# EFT_X003_Y003_X007.net
KiCad netlist of a schematic drawn in EasyEDA Pro
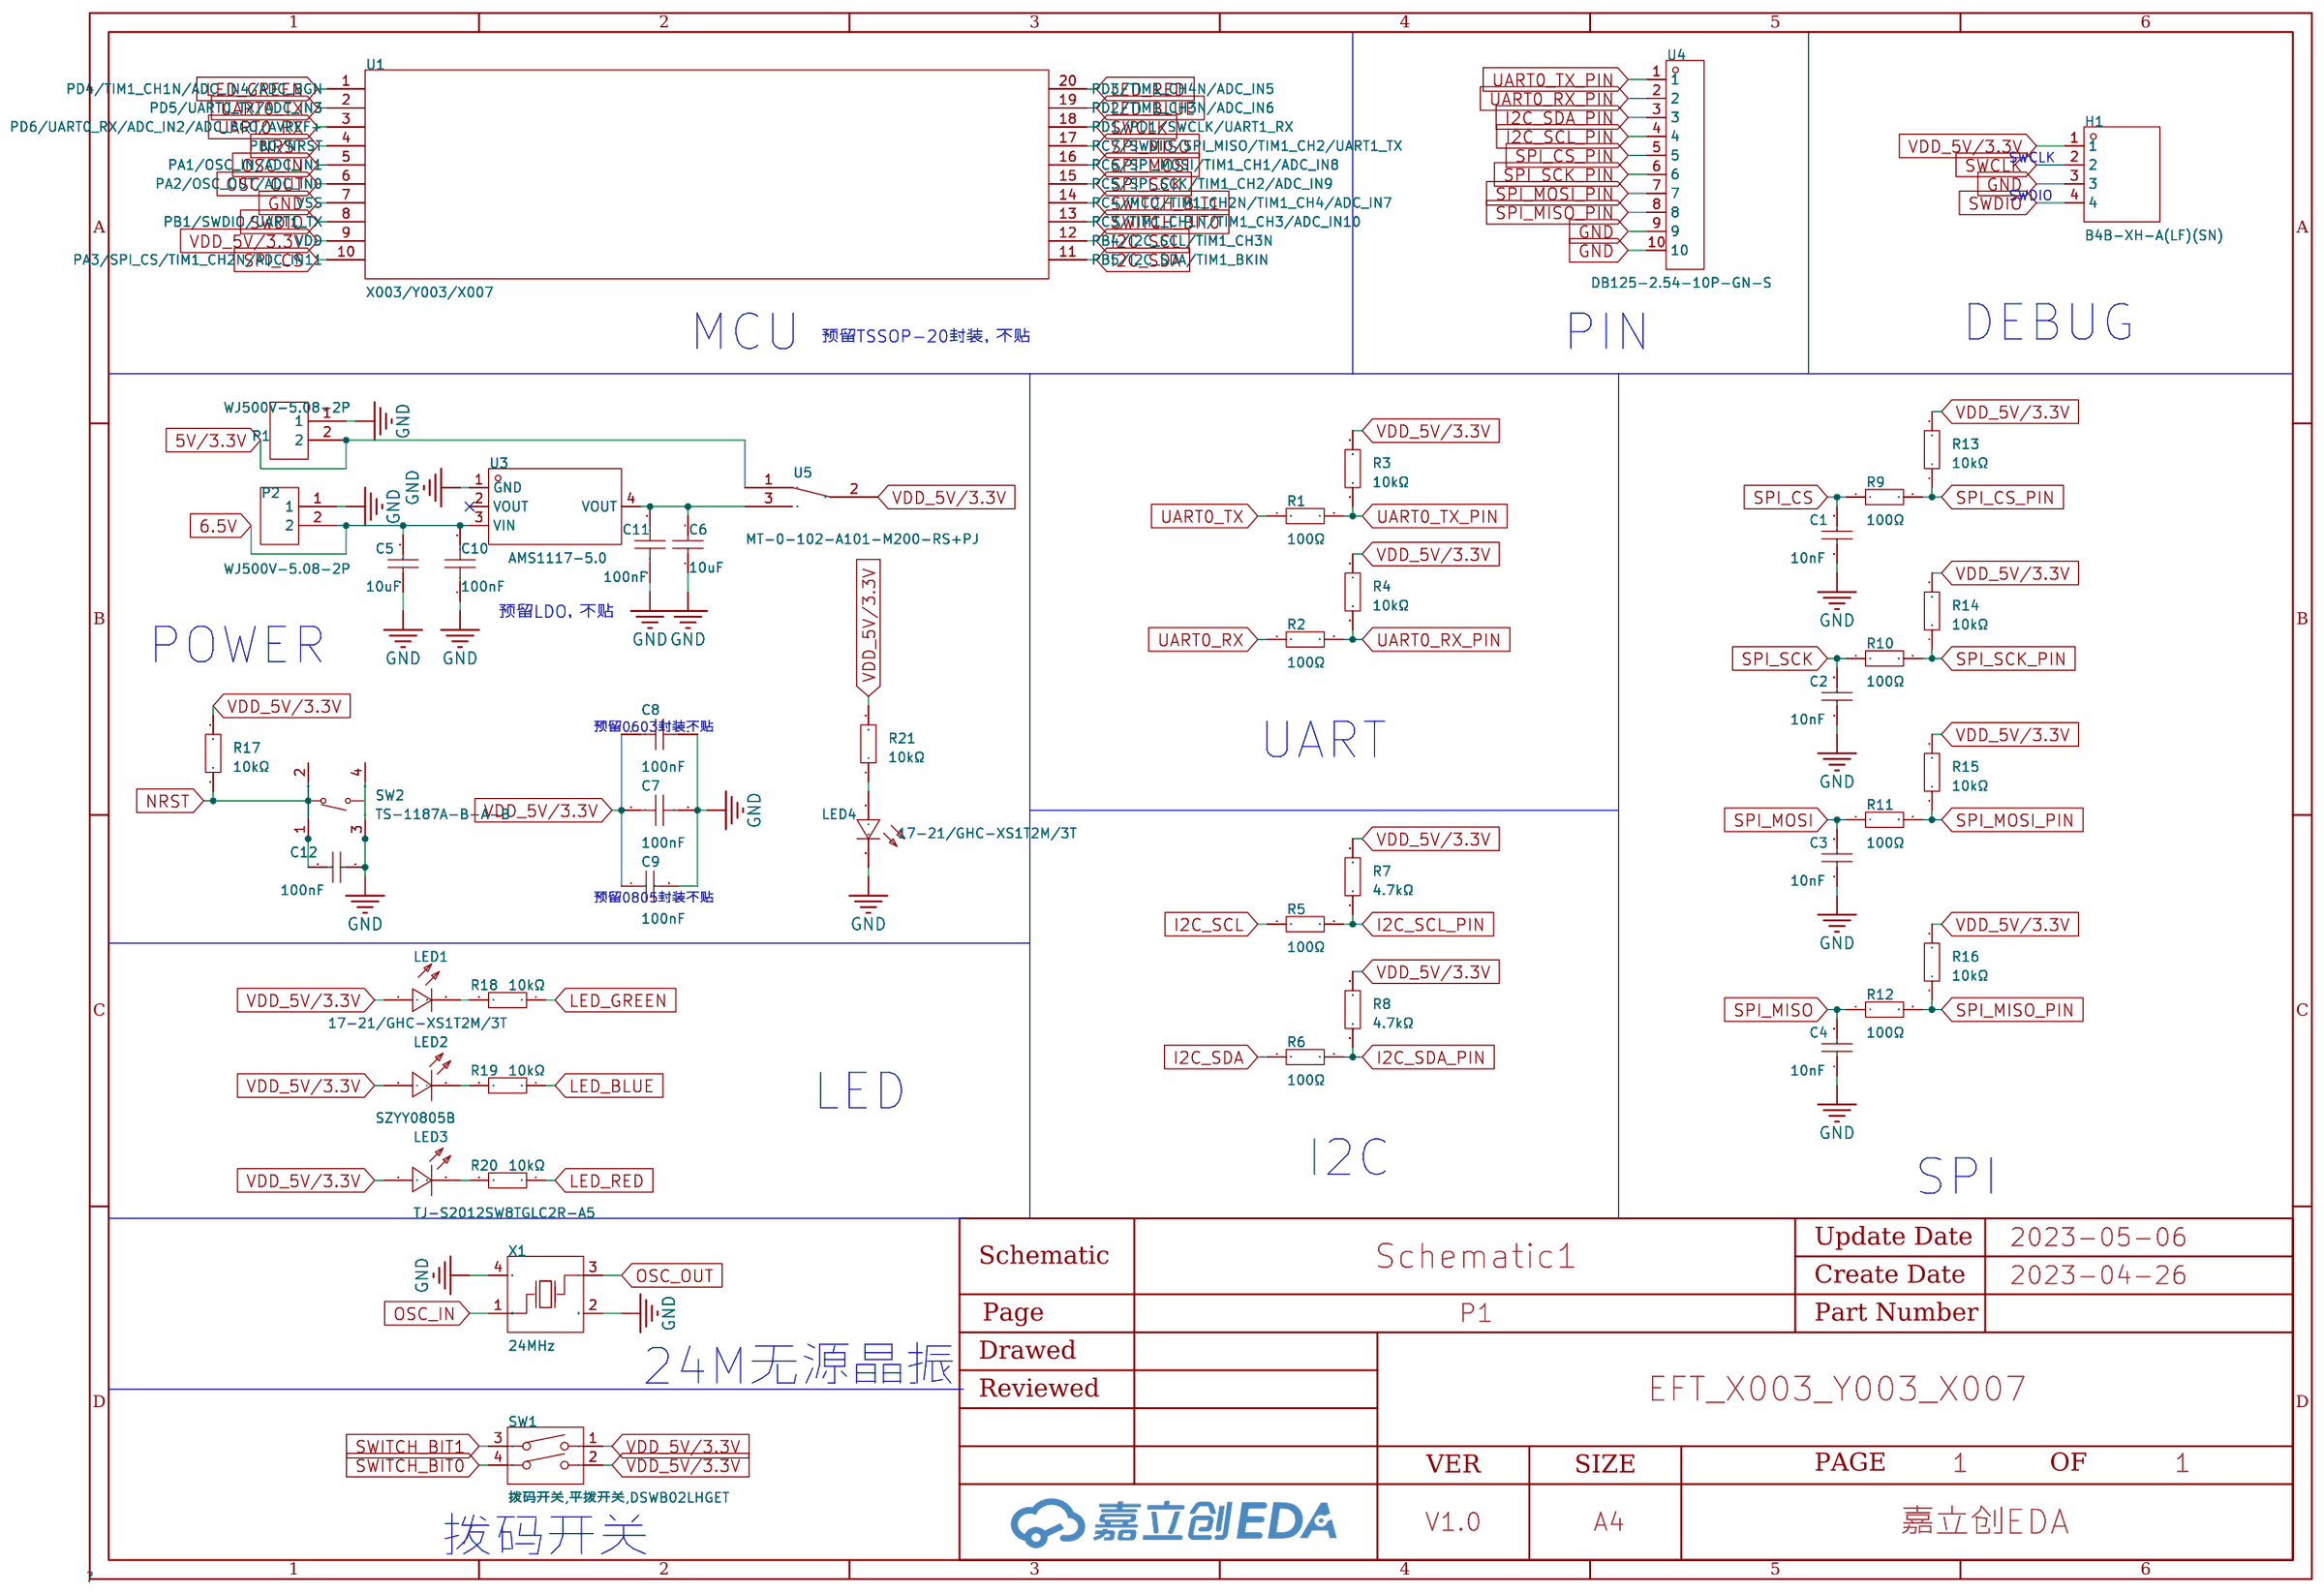
[diagram p0: schematic sheet]

(export (version "E")
  (design (tool "Eeschema 10.0.6"))
  (components
    (comp (ref "C1")
      (value "10nF")
      (footprint "easyedapro:C0805")
      (description "容值:10nF;精度:±10%;额定电压:50V;材质(温度系数):X7R;")
      (fields
        (field (name "Manufacturer Part") "CL21B103KBANNNC")
        (field (name "Manufacturer") "SAMSUNG(三星)")
      )
      (libsource (lib "easyedapro") (part "CL21B103KBANNNC"))
    )
    (comp (ref "C2")
      (value "10nF")
      (footprint "easyedapro:C0805")
      (description "容值:10nF;精度:±10%;额定电压:50V;材质(温度系数):X7R;")
      (fields
        (field (name "Manufacturer Part") "CL21B103KBANNNC")
        (field (name "Manufacturer") "SAMSUNG(三星)")
      )
      (libsource (lib "easyedapro") (part "CL21B103KBANNNC"))
    )
    (comp (ref "C3")
      (value "10nF")
      (footprint "easyedapro:C0805")
      (description "容值:10nF;精度:±10%;额定电压:50V;材质(温度系数):X7R;")
      (fields
        (field (name "Manufacturer Part") "CL21B103KBANNNC")
        (field (name "Manufacturer") "SAMSUNG(三星)")
      )
      (libsource (lib "easyedapro") (part "CL21B103KBANNNC"))
    )
    (comp (ref "C4")
      (value "10nF")
      (footprint "easyedapro:C0805")
      (description "容值:10nF;精度:±10%;额定电压:50V;材质(温度系数):X7R;")
      (fields
        (field (name "Manufacturer Part") "CL21B103KBANNNC")
        (field (name "Manufacturer") "SAMSUNG(三星)")
      )
      (libsource (lib "easyedapro") (part "CL21B103KBANNNC"))
    )
    (comp (ref "C5")
      (value "10uF")
      (footprint "easyedapro:C0805")
      (description "容值:10uF;精度:±10%;额定电压:25V;材质(温度系数):X5R;")
      (fields
        (field (name "Manufacturer Part") "CL21A106KAYNNNE")
        (field (name "Manufacturer") "SAMSUNG(三星)")
      )
      (libsource (lib "easyedapro") (part "CL21A106KAYNNNE"))
    )
    (comp (ref "C6")
      (value "10uF")
      (footprint "easyedapro:C0805")
      (description "容值:10uF;精度:±10%;额定电压:25V;材质(温度系数):X5R;")
      (fields
        (field (name "Manufacturer Part") "CL21A106KAYNNNE")
        (field (name "Manufacturer") "SAMSUNG(三星)")
      )
      (libsource (lib "easyedapro") (part "CL21A106KAYNNNE"))
    )
    (comp (ref "C7")
      (value "100nF")
      (footprint "easyedapro:C0603")
      (description "容值:100nF;精度:±10%;额定电压:50V;材质(温度系数):X7R;")
      (fields
        (field (name "Manufacturer Part") "CC0603KRX7R9BB104")
        (field (name "Manufacturer") "YAGEO(国巨)")
      )
      (libsource (lib "easyedapro") (part "CC0603KRX7R9BB104"))
    )
    (comp (ref "C8")
      (value "100nF")
      (footprint "easyedapro:C0603")
      (description "容值:100nF;精度:±10%;额定电压:50V;材质(温度系数):X7R;")
      (fields
        (field (name "Manufacturer Part") "CC0603KRX7R9BB104")
        (field (name "Manufacturer") "YAGEO(国巨)")
      )
      (libsource (lib "easyedapro") (part "CC0603KRX7R9BB104"))
    )
    (comp (ref "C9")
      (value "100nF")
      (footprint "easyedapro:C0805")
      (description "容值:100nF;精度:±10%;额定电压:50V;材质(温度系数):X7R;")
      (fields
        (field (name "Manufacturer Part") "CC0805KRX7R9BB104")
        (field (name "Manufacturer") "YAGEO(国巨)")
      )
      (libsource (lib "easyedapro") (part "CC0805KRX7R9BB104"))
    )
    (comp (ref "C10")
      (value "100nF")
      (footprint "easyedapro:C0603")
      (description "容值:100nF;精度:±10%;额定电压:50V;材质(温度系数):X7R;")
      (fields
        (field (name "Manufacturer Part") "CL10B104KB8NNNC")
        (field (name "Manufacturer") "SAMSUNG(三星)")
      )
      (libsource (lib "easyedapro") (part "CL10B104KB8NNNC"))
    )
    (comp (ref "C11")
      (value "100nF")
      (footprint "easyedapro:C0603")
      (description "容值:100nF;精度:±10%;额定电压:50V;材质(温度系数):X7R;")
      (fields
        (field (name "Manufacturer Part") "CL10B104KB8NNNC")
        (field (name "Manufacturer") "SAMSUNG(三星)")
      )
      (libsource (lib "easyedapro") (part "CL10B104KB8NNNC"))
    )
    (comp (ref "C12")
      (value "100nF")
      (footprint "easyedapro:C0603")
      (description "容值:100nF;精度:±10%;额定电压:50V;材质(温度系数):X7R;")
      (fields (field (name "Manufacturer Part") "0603B104K500NT") (field (name "Manufacturer") "FH(风华)"))
      (libsource (lib "easyedapro") (part "0603B104K500NT"))
    )
    (comp (ref "H1")
      (value "B4B-XH-A(LF)(SN)")
      (footprint "easyedapro:CONN-TH_B4B-XH-A-LF-SN")
      (description "参考系列:XH;间距:2.5mm;插针结构:1x4P;排数:1;每排PIN数:4;行距:-;安装方式:-;触头材质:黄铜;")
      (fields (field (name "Manufacturer") "JST"))
      (libsource (lib "easyedapro") (part "B4B-XH-A(LF)(SN)"))
    )
    (comp (ref "LED1")
      (value "17-21/GHC-XS1T2M/3T")
      (footprint "easyedapro:LED0805-R-RD")
      (description "发光颜色:翠绿;二极管配置:-;主波长:515nm~530nm;色温:-;功率:75mW;安装方式:-;")
      (fields (field (name "Manufacturer") "EVERLIGHT(亿光)"))
      (libsource (lib "easyedapro") (part "17-21/GHC-XS1T2M/3T"))
    )
    (comp (ref "LED2")
      (value "SZYY0805B")
      (footprint "easyedapro:LED0805-R-RD_BLUE")
      (description "发光颜色:蓝灯;二极管配置:-;主波长:460nm~475nm;色温:-;功率:100mW;安装方式:-;")
      (fields (field (name "Manufacturer") "yongyu(永裕光电)"))
      (libsource (lib "easyedapro") (part "SZYY0805B"))
    )
    (comp (ref "LED3")
      (value "TJ-S2012SW8TGLC2R-A5")
      (footprint "easyedapro:LED0805-R-RD")
      (description "发光颜色:红灯;二极管配置:-;主波长:620nm;色温:-;功率:72mW;安装方式:-;")
      (fields (field (name "Manufacturer") "TOGIALED(统佳)"))
      (libsource (lib "easyedapro") (part "TJ-S2012SW8TGLC2R-A5"))
    )
    (comp (ref "LED4")
      (value "17-21/GHC-XS1T2M/3T")
      (footprint "easyedapro:LED0805-R-RD")
      (description "发光颜色:翠绿;二极管配置:-;主波长:515nm~530nm;色温:-;功率:75mW;安装方式:-;")
      (fields (field (name "Manufacturer") "EVERLIGHT(亿光)"))
      (libsource (lib "easyedapro") (part "17-21/GHC-XS1T2M/3T"))
    )
    (comp (ref "P1")
      (value "WJ500V-5.08-2P")
      (footprint "easyedapro:CONN-TH_2P-P5.00_WJ500V-5.08-2P")
      (fields (field (name "Manufacturer") "KANGNEX(康奈克斯电气)"))
      (libsource (lib "easyedapro") (part "WJ500V-5.08-2P-14-00A"))
    )
    (comp (ref "P2")
      (value "WJ500V-5.08-2P")
      (footprint "easyedapro:CONN-TH_2P-P5.00_WJ500V-5.08-2P")
      (fields (field (name "Manufacturer") "KANGNEX(康奈克斯电气)"))
      (libsource (lib "easyedapro") (part "WJ500V-5.08-2P-14-00A"))
    )
    (comp (ref "R1")
      (value "100Ω")
      (footprint "easyedapro:R0805")
      (description "电阻类型:厚膜电阻;阻值:100Ω;精度:±1%;功率:125mW;")
      (fields
        (field (name "Manufacturer Part") "0805W8F1000T5E")
        (field (name "Manufacturer") "UNI-ROYAL(厚声)")
      )
      (libsource (lib "easyedapro") (part "0805W8F1000T5E"))
    )
    (comp (ref "R2")
      (value "100Ω")
      (footprint "easyedapro:R0805")
      (description "电阻类型:厚膜电阻;阻值:100Ω;精度:±1%;功率:125mW;")
      (fields
        (field (name "Manufacturer Part") "0805W8F1000T5E")
        (field (name "Manufacturer") "UNI-ROYAL(厚声)")
      )
      (libsource (lib "easyedapro") (part "0805W8F1000T5E"))
    )
    (comp (ref "R3")
      (value "10kΩ")
      (footprint "easyedapro:R0805")
      (description "电阻类型:厚膜电阻;阻值:10kΩ;精度:±1%;功率:125mW;")
      (fields
        (field (name "Manufacturer Part") "0805W8F1002T5E")
        (field (name "Manufacturer") "UNI-ROYAL(厚声)")
      )
      (libsource (lib "easyedapro") (part "0805W8F1002T5E"))
    )
    (comp (ref "R4")
      (value "10kΩ")
      (footprint "easyedapro:R0805")
      (description "电阻类型:厚膜电阻;阻值:10kΩ;精度:±1%;功率:125mW;")
      (fields
        (field (name "Manufacturer Part") "0805W8F1002T5E")
        (field (name "Manufacturer") "UNI-ROYAL(厚声)")
      )
      (libsource (lib "easyedapro") (part "0805W8F1002T5E"))
    )
    (comp (ref "R5")
      (value "100Ω")
      (footprint "easyedapro:R0805")
      (description "电阻类型:厚膜电阻;阻值:100Ω;精度:±1%;功率:125mW;")
      (fields
        (field (name "Manufacturer Part") "0805W8F1000T5E")
        (field (name "Manufacturer") "UNI-ROYAL(厚声)")
      )
      (libsource (lib "easyedapro") (part "0805W8F1000T5E"))
    )
    (comp (ref "R6")
      (value "100Ω")
      (footprint "easyedapro:R0805")
      (description "电阻类型:厚膜电阻;阻值:100Ω;精度:±1%;功率:125mW;")
      (fields
        (field (name "Manufacturer Part") "0805W8F1000T5E")
        (field (name "Manufacturer") "UNI-ROYAL(厚声)")
      )
      (libsource (lib "easyedapro") (part "0805W8F1000T5E"))
    )
    (comp (ref "R7")
      (value "4.7kΩ")
      (footprint "easyedapro:R0805")
      (description "电阻类型:厚膜电阻;阻值:4.7kΩ;精度:±1%;功率:125mW;")
      (fields
        (field (name "Manufacturer Part") "0805W8F4701T5E")
        (field (name "Manufacturer") "UNI-ROYAL(厚声)")
      )
      (libsource (lib "easyedapro") (part "0805W8F4701T5E"))
    )
    (comp (ref "R8")
      (value "4.7kΩ")
      (footprint "easyedapro:R0805")
      (description "电阻类型:厚膜电阻;阻值:4.7kΩ;精度:±1%;功率:125mW;")
      (fields
        (field (name "Manufacturer Part") "0805W8F4701T5E")
        (field (name "Manufacturer") "UNI-ROYAL(厚声)")
      )
      (libsource (lib "easyedapro") (part "0805W8F4701T5E"))
    )
    (comp (ref "R9")
      (value "100Ω")
      (footprint "easyedapro:R0805")
      (description "电阻类型:厚膜电阻;阻值:100Ω;精度:±1%;功率:125mW;")
      (fields
        (field (name "Manufacturer Part") "0805W8F1000T5E")
        (field (name "Manufacturer") "UNI-ROYAL(厚声)")
      )
      (libsource (lib "easyedapro") (part "0805W8F1000T5E"))
    )
    (comp (ref "R10")
      (value "100Ω")
      (footprint "easyedapro:R0805")
      (description "电阻类型:厚膜电阻;阻值:100Ω;精度:±1%;功率:125mW;")
      (fields
        (field (name "Manufacturer Part") "0805W8F1000T5E")
        (field (name "Manufacturer") "UNI-ROYAL(厚声)")
      )
      (libsource (lib "easyedapro") (part "0805W8F1000T5E"))
    )
    (comp (ref "R11")
      (value "100Ω")
      (footprint "easyedapro:R0805")
      (description "电阻类型:厚膜电阻;阻值:100Ω;精度:±1%;功率:125mW;")
      (fields
        (field (name "Manufacturer Part") "0805W8F1000T5E")
        (field (name "Manufacturer") "UNI-ROYAL(厚声)")
      )
      (libsource (lib "easyedapro") (part "0805W8F1000T5E"))
    )
    (comp (ref "R12")
      (value "100Ω")
      (footprint "easyedapro:R0805")
      (description "电阻类型:厚膜电阻;阻值:100Ω;精度:±1%;功率:125mW;")
      (fields
        (field (name "Manufacturer Part") "0805W8F1000T5E")
        (field (name "Manufacturer") "UNI-ROYAL(厚声)")
      )
      (libsource (lib "easyedapro") (part "0805W8F1000T5E"))
    )
    (comp (ref "R13")
      (value "10kΩ")
      (footprint "easyedapro:R0805")
      (description "电阻类型:厚膜电阻;阻值:10kΩ;精度:±1%;功率:125mW;")
      (fields
        (field (name "Manufacturer Part") "0805W8F1002T5E")
        (field (name "Manufacturer") "UNI-ROYAL(厚声)")
      )
      (libsource (lib "easyedapro") (part "0805W8F1002T5E"))
    )
    (comp (ref "R14")
      (value "10kΩ")
      (footprint "easyedapro:R0805")
      (description "电阻类型:厚膜电阻;阻值:10kΩ;精度:±1%;功率:125mW;")
      (fields
        (field (name "Manufacturer Part") "0805W8F1002T5E")
        (field (name "Manufacturer") "UNI-ROYAL(厚声)")
      )
      (libsource (lib "easyedapro") (part "0805W8F1002T5E"))
    )
    (comp (ref "R15")
      (value "10kΩ")
      (footprint "easyedapro:R0805")
      (description "电阻类型:厚膜电阻;阻值:10kΩ;精度:±1%;功率:125mW;")
      (fields
        (field (name "Manufacturer Part") "0805W8F1002T5E")
        (field (name "Manufacturer") "UNI-ROYAL(厚声)")
      )
      (libsource (lib "easyedapro") (part "0805W8F1002T5E"))
    )
    (comp (ref "R16")
      (value "10kΩ")
      (footprint "easyedapro:R0805")
      (description "电阻类型:厚膜电阻;阻值:10kΩ;精度:±1%;功率:125mW;")
      (fields
        (field (name "Manufacturer Part") "0805W8F1002T5E")
        (field (name "Manufacturer") "UNI-ROYAL(厚声)")
      )
      (libsource (lib "easyedapro") (part "0805W8F1002T5E"))
    )
    (comp (ref "R17")
      (value "10kΩ")
      (footprint "easyedapro:R0805")
      (description "阻值:10kΩ;精度:±1%;功率:125mW;温度系数:±100ppm/°C;最大工作电压:150V;工作温度范围:-55°C~+155°C;")
      (fields (field (name "Manufacturer Part") "RC0805FR-0710KL") (field (name "Manufacturer") "YAGEO(国巨)"))
      (libsource (lib "easyedapro") (part "RC0805FR-0710KL"))
    )
    (comp (ref "R18")
      (value "10kΩ")
      (footprint "easyedapro:R0805")
      (description "阻值:10kΩ;精度:±1%;功率:125mW;温度系数:±100ppm/°C;最大工作电压:150V;工作温度范围:-55°C~+155°C;")
      (fields (field (name "Manufacturer Part") "RC0805FR-0710KL") (field (name "Manufacturer") "YAGEO(国巨)"))
      (libsource (lib "easyedapro") (part "RC0805FR-0710KL"))
    )
    (comp (ref "R19")
      (value "10kΩ")
      (footprint "easyedapro:R0805")
      (description "阻值:10kΩ;精度:±1%;功率:125mW;温度系数:±100ppm/°C;最大工作电压:150V;工作温度范围:-55°C~+155°C;")
      (fields (field (name "Manufacturer Part") "RC0805FR-0710KL") (field (name "Manufacturer") "YAGEO(国巨)"))
      (libsource (lib "easyedapro") (part "RC0805FR-0710KL"))
    )
    (comp (ref "R20")
      (value "10kΩ")
      (footprint "easyedapro:R0805")
      (description "阻值:10kΩ;精度:±1%;功率:125mW;温度系数:±100ppm/°C;最大工作电压:150V;工作温度范围:-55°C~+155°C;")
      (fields (field (name "Manufacturer Part") "RC0805FR-0710KL") (field (name "Manufacturer") "YAGEO(国巨)"))
      (libsource (lib "easyedapro") (part "RC0805FR-0710KL"))
    )
    (comp (ref "R21")
      (value "10kΩ")
      (footprint "easyedapro:R0805")
      (description "阻值:10kΩ;精度:±1%;功率:125mW;温度系数:±100ppm/°C;最大工作电压:150V;工作温度范围:-55°C~+155°C;")
      (fields (field (name "Manufacturer Part") "RC0805FR-0710KL") (field (name "Manufacturer") "YAGEO(国巨)"))
      (libsource (lib "easyedapro") (part "RC0805FR-0710KL"))
    )
    (comp (ref "SW1")
      (value "拨码开关,平拨开关,DSWB02LHGET")
      (footprint "easyedapro:SW-TH_DSWB02LHGET")
      (description "类型:平拨，凸起式;电路结构:单刀单掷;开关位数:2;引脚间距:2.54mm;颜色:红色;")
      (fields (field (name "Manufacturer") "YE"))
      (libsource (lib "easyedapro") (part "DSWB02LHGET"))
    )
    (comp (ref "SW2")
      (value "TS-1187A-B-A-B")
      (footprint "easyedapro:SW-SMD_4P-L5.1-W5.1-P3.70-LS6.5-TL-2")
      (description "触点电流:50mA;额定电压(DC):12V;绝缘电阻:-;电路结构:单刀单掷;安装方式:立贴;带灯:无;作用力:160gf;机械寿命:10万次;带支架:否;")
      (fields (field (name "Manufacturer") "XKB Connectivity(中国星坤)"))
      (libsource (lib "easyedapro") (part "TS-1187A-B-A-B"))
    )
    (comp (ref "U1")
      (value "X003/Y003/X007")
      (footprint "easyedapro:TSSOP-20_L6.5-W4.4-P0.65-LS6.4-BL")
      (libsource (lib "easyedapro") (part "PT32Y003"))
    )
    (comp (ref "U3")
      (value "AMS1117-5.0")
      (footprint "easyedapro:SOT-223_L6.5-W3.5-P2.30-LS7.0-BR")
      (description "输出类型:固定;输出极性:正;最大输入电压:15V;输出电压:5V;输出电流:1A;电源纹波抑制比(PSRR):68dB@(120Hz);")
      (fields (field (name "Manufacturer") "AMS"))
      (libsource (lib "easyedapro") (part "AMS1117-5.0"))
    )
    (comp (ref "U4")
      (value "DB125-2.54-10P-GN-S")
      (footprint "easyedapro:CONN-TH_DB125-2.54-10P-GN")
      (fields (field (name "Manufacturer") "DIBO(地博电气)"))
      (libsource (lib "easyedapro") (part "DB125-2.54-10P-GN"))
    )
    (comp (ref "U5")
      (value "MT-0-102-A101-M200-RS+PJ")
      (footprint "easyedapro:SW-TH_MT-0-103-A101-M200-RS")
      (description "额定电流:5A;额定电压(AC):125V;电路结构:单刀双掷;机械寿命:-;安装方式:直插;")
      (fields (field (name "Manufacturer") "YUEN FUNG(源丰)"))
      (libsource (lib "easyedapro") (part "MT-0-102-A101-M200-RS+PJ"))
    )
    (comp (ref "X1")
      (value "24MHz")
      (footprint "easyedapro:CRYSTAL-SMD_4P-L3.2-W2.5-BL")
      (description "频率:24MHz;频率公差:±10ppm;频率稳定度:±50ppm;负载电容:8pF;")
      (fields (field (name "Manufacturer Part") "3S24000333") (field (name "Manufacturer") "YL(惠伦晶体)"))
      (libsource (lib "easyedapro") (part "3S24000333"))
    )
  )
  (nets
    (net (code "1") (name "5V{slash}3.3V") (class "Default")
      (node (ref "P1") (pin "2") (pinfunction "2_2") (pintype "input"))
      (node (ref "U5") (pin "1") (pinfunction "1_1") (pintype "input"))
    )
    (net (code "2") (name "6.5V") (class "Default")
      (node (ref "C10") (pin "2") (pinfunction "2_2") (pintype "input"))
      (node (ref "C5") (pin "2") (pinfunction "2_2") (pintype "input"))
      (node (ref "P2") (pin "2") (pinfunction "2_2") (pintype "input"))
      (node (ref "U3") (pin "3") (pinfunction "VIN_3") (pintype "input"))
    )
    (net (code "3") (name "GND") (class "Default")
      (node (ref "C1") (pin "1") (pinfunction "1_1") (pintype "input"))
      (node (ref "C10") (pin "1") (pinfunction "1_1") (pintype "input"))
      (node (ref "C11") (pin "1") (pinfunction "1_1") (pintype "input"))
      (node (ref "C12") (pin "2") (pinfunction "2_2") (pintype "input"))
      (node (ref "C2") (pin "1") (pinfunction "1_1") (pintype "input"))
      (node (ref "C3") (pin "1") (pinfunction "1_1") (pintype "input"))
      (node (ref "C4") (pin "1") (pinfunction "1_1") (pintype "input"))
      (node (ref "C5") (pin "1") (pinfunction "1_1") (pintype "input"))
      (node (ref "C6") (pin "1") (pinfunction "1_1") (pintype "input"))
      (node (ref "C7") (pin "2") (pinfunction "2_2") (pintype "input"))
      (node (ref "C8") (pin "2") (pinfunction "2_2") (pintype "input"))
      (node (ref "C9") (pin "2") (pinfunction "2_2") (pintype "input"))
      (node (ref "H1") (pin "3") (pinfunction "3_3") (pintype "input"))
      (node (ref "LED4") (pin "2") (pinfunction "C_2") (pintype "input"))
      (node (ref "P1") (pin "1") (pinfunction "1_1") (pintype "input"))
      (node (ref "P2") (pin "1") (pinfunction "1_1") (pintype "input"))
      (node (ref "SW2") (pin "3") (pinfunction "C_3") (pintype "input"))
      (node (ref "SW2") (pin "4") (pinfunction "D_4") (pintype "input"))
      (node (ref "U1") (pin "7") (pinfunction "VSS_7") (pintype "input"))
      (node (ref "U3") (pin "1") (pinfunction "GND_1") (pintype "input"))
      (node (ref "U4") (pin "10") (pinfunction "10_10") (pintype "input"))
      (node (ref "U4") (pin "9") (pinfunction "9_9") (pintype "input"))
      (node (ref "X1") (pin "2") (pinfunction "GND_2") (pintype "input"))
      (node (ref "X1") (pin "4") (pinfunction "GND_4") (pintype "input"))
    )
    (net (code "4") (name "I2C_SCL") (class "Default")
      (node (ref "R5") (pin "1") (pinfunction "1_1") (pintype "input"))
      (node (ref "U1") (pin "12") (pinfunction "PB4/I2C_SCL/TIM1_CH3N_12") (pintype "input"))
    )
    (net (code "5") (name "I2C_SCL_PIN") (class "Default")
      (node (ref "R5") (pin "2") (pinfunction "2_2") (pintype "input"))
      (node (ref "R7") (pin "1") (pinfunction "1_1") (pintype "input"))
      (node (ref "U4") (pin "4") (pinfunction "4_4") (pintype "input"))
    )
    (net (code "6") (name "I2C_SDA") (class "Default")
      (node (ref "R6") (pin "1") (pinfunction "1_1") (pintype "input"))
      (node (ref "U1") (pin "11") (pinfunction "PB5/I2C_SDA/TIM1_BKIN_11") (pintype "input"))
    )
    (net (code "7") (name "I2C_SDA_PIN") (class "Default")
      (node (ref "R6") (pin "2") (pinfunction "2_2") (pintype "input"))
      (node (ref "R8") (pin "1") (pinfunction "1_1") (pintype "input"))
      (node (ref "U4") (pin "3") (pinfunction "3_3") (pintype "input"))
    )
    (net (code "8") (name "LED_BLUE") (class "Default")
      (node (ref "R19") (pin "1") (pinfunction "1_1") (pintype "input"))
      (node (ref "U1") (pin "19") (pinfunction "PD2/TIM1_CH3N/ADC_IN6_19") (pintype "input"))
    )
    (net (code "9") (name "LED_GREEN") (class "Default")
      (node (ref "R18") (pin "1") (pinfunction "1_1") (pintype "input"))
      (node (ref "U1") (pin "1") (pinfunction "PD4/TIM1_CH1N/ADC_IN4/ADC_BGN_1") (pintype "input"))
    )
    (net (code "10") (name "LED_RED") (class "Default")
      (node (ref "R20") (pin "1") (pinfunction "1_1") (pintype "input"))
      (node (ref "U1") (pin "20") (pinfunction "PD3/TIM1_CH4N/ADC_IN5_20") (pintype "input"))
    )
    (net (code "11") (name "NRST") (class "Default")
      (node (ref "C12") (pin "1") (pinfunction "1_1") (pintype "input"))
      (node (ref "R17") (pin "1") (pinfunction "1_1") (pintype "input"))
      (node (ref "SW2") (pin "1") (pinfunction "A_1") (pintype "input"))
      (node (ref "SW2") (pin "2") (pinfunction "B_2") (pintype "input"))
      (node (ref "U1") (pin "4") (pinfunction "PB0/NRST_4") (pintype "input"))
    )
    (net (code "12") (name "Net-(C11-Pad2)") (class "Default")
      (node (ref "C11") (pin "2") (pinfunction "2_2") (pintype "input"))
      (node (ref "C6") (pin "2") (pinfunction "2_2") (pintype "input"))
      (node (ref "U3") (pin "4") (pinfunction "VOUT_4") (pintype "input"))
      (node (ref "U5") (pin "3") (pinfunction "3_3") (pintype "input"))
    )
    (net (code "13") (name "Net-(LED1-C)") (class "Default")
      (node (ref "LED1") (pin "2") (pinfunction "C_2") (pintype "input"))
      (node (ref "R18") (pin "2") (pinfunction "2_2") (pintype "input"))
    )
    (net (code "14") (name "Net-(LED2--)") (class "Default")
      (node (ref "LED2") (pin "2") (pinfunction "-_2") (pintype "input"))
      (node (ref "R19") (pin "2") (pinfunction "2_2") (pintype "input"))
    )
    (net (code "15") (name "Net-(LED3-C)") (class "Default")
      (node (ref "LED3") (pin "2") (pinfunction "C_2") (pintype "input"))
      (node (ref "R20") (pin "2") (pinfunction "2_2") (pintype "input"))
    )
    (net (code "16") (name "Net-(LED4-A)") (class "Default")
      (node (ref "LED4") (pin "1") (pinfunction "A_1") (pintype "input"))
      (node (ref "R21") (pin "1") (pinfunction "1_1") (pintype "input"))
    )
    (net (code "17") (name "OSC_IN") (class "Default")
      (node (ref "U1") (pin "5") (pinfunction "PA1/OSC_IN/ADC_IN1_5") (pintype "input"))
      (node (ref "X1") (pin "1") (pinfunction "OSC1_1") (pintype "input"))
    )
    (net (code "18") (name "OSC_OUT") (class "Default")
      (node (ref "U1") (pin "6") (pinfunction "PA2/OSC_OUT/ADC_IN0_6") (pintype "input"))
      (node (ref "X1") (pin "3") (pinfunction "OSC2_3") (pintype "input"))
    )
    (net (code "19") (name "SPI_CS") (class "Default")
      (node (ref "C1") (pin "2") (pinfunction "2_2") (pintype "input"))
      (node (ref "R9") (pin "1") (pinfunction "1_1") (pintype "input"))
      (node (ref "U1") (pin "10") (pinfunction "PA3/SPI_CS/TIM1_CH2N/ADC_IN11_10") (pintype "input"))
    )
    (net (code "20") (name "SPI_CS_PIN") (class "Default")
      (node (ref "R13") (pin "1") (pinfunction "1_1") (pintype "input"))
      (node (ref "R9") (pin "2") (pinfunction "2_2") (pintype "input"))
      (node (ref "U4") (pin "5") (pinfunction "5_5") (pintype "input"))
    )
    (net (code "21") (name "SPI_MISO") (class "Default")
      (node (ref "C4") (pin "2") (pinfunction "2_2") (pintype "input"))
      (node (ref "R12") (pin "1") (pinfunction "1_1") (pintype "input"))
      (node (ref "U1") (pin "17") (pinfunction "PC7/SWDIO/SPI_MISO/TIM1_CH2/UART1_TX_17") (pintype "input"))
    )
    (net (code "22") (name "SPI_MISO_PIN") (class "Default")
      (node (ref "R12") (pin "2") (pinfunction "2_2") (pintype "input"))
      (node (ref "R16") (pin "1") (pinfunction "1_1") (pintype "input"))
      (node (ref "U4") (pin "8") (pinfunction "8_8") (pintype "input"))
    )
    (net (code "23") (name "SPI_MOSI") (class "Default")
      (node (ref "C3") (pin "2") (pinfunction "2_2") (pintype "input"))
      (node (ref "R11") (pin "1") (pinfunction "1_1") (pintype "input"))
      (node (ref "U1") (pin "16") (pinfunction "PC6/SPI_MOSI/TIM1_CH1/ADC_IN8_16") (pintype "input"))
    )
    (net (code "24") (name "SPI_MOSI_PIN") (class "Default")
      (node (ref "R11") (pin "2") (pinfunction "2_2") (pintype "input"))
      (node (ref "R15") (pin "1") (pinfunction "1_1") (pintype "input"))
      (node (ref "U4") (pin "7") (pinfunction "7_7") (pintype "input"))
    )
    (net (code "25") (name "SPI_SCK") (class "Default")
      (node (ref "C2") (pin "2") (pinfunction "2_2") (pintype "input"))
      (node (ref "R10") (pin "1") (pinfunction "1_1") (pintype "input"))
      (node (ref "U1") (pin "15") (pinfunction "PC5/SPI_SCK/TIM1_CH2/ADC_IN9_15") (pintype "input"))
    )
    (net (code "26") (name "SPI_SCK_PIN") (class "Default")
      (node (ref "R10") (pin "2") (pinfunction "2_2") (pintype "input"))
      (node (ref "R14") (pin "1") (pinfunction "1_1") (pintype "input"))
      (node (ref "U4") (pin "6") (pinfunction "6_6") (pintype "input"))
    )
    (net (code "27") (name "SWCLK") (class "Default")
      (node (ref "H1") (pin "2") (pinfunction "2_2") (pintype "input"))
      (node (ref "U1") (pin "18") (pinfunction "PD1/PD1/SWCLK/UART1_RX_18") (pintype "input"))
    )
    (net (code "28") (name "SWDIO") (class "Default")
      (node (ref "H1") (pin "4") (pinfunction "4_4") (pintype "input"))
      (node (ref "U1") (pin "8") (pinfunction "PB1/SWDIO/UART1_TX_8") (pintype "input"))
    )
    (net (code "29") (name "SWITCH_BIT0") (class "Default")
      (node (ref "SW1") (pin "4") (pinfunction "4_4") (pintype "input"))
      (node (ref "U1") (pin "13") (pinfunction "PC3/TIM1_CH1N/TIM1_CH3/ADC_IN10_13") (pintype "input"))
    )
    (net (code "30") (name "SWITCH_BIT1") (class "Default")
      (node (ref "SW1") (pin "3") (pinfunction "3_3") (pintype "input"))
      (node (ref "U1") (pin "14") (pinfunction "PC4/MCO/TIM1_CH2N/TIM1_CH4/ADC_IN7_14") (pintype "input"))
    )
    (net (code "31") (name "UART0_RX") (class "Default")
      (node (ref "R2") (pin "1") (pinfunction "1_1") (pintype "input"))
      (node (ref "U1") (pin "3") (pinfunction "PD6/UART0_RX/ADC_IN2/ADC_BGO/AVREF+_3") (pintype "input"))
    )
    (net (code "32") (name "UART0_RX_PIN") (class "Default")
      (node (ref "R2") (pin "2") (pinfunction "2_2") (pintype "input"))
      (node (ref "R4") (pin "2") (pinfunction "2_2") (pintype "input"))
      (node (ref "U4") (pin "2") (pinfunction "2_2") (pintype "input"))
    )
    (net (code "33") (name "UART0_TX") (class "Default")
      (node (ref "R1") (pin "1") (pinfunction "1_1") (pintype "input"))
      (node (ref "U1") (pin "2") (pinfunction "PD5/UART0_TX/ADC_IN3_2") (pintype "input"))
    )
    (net (code "34") (name "UART0_TX_PIN") (class "Default")
      (node (ref "R1") (pin "2") (pinfunction "2_2") (pintype "input"))
      (node (ref "R3") (pin "1") (pinfunction "1_1") (pintype "input"))
      (node (ref "U4") (pin "1") (pinfunction "1_1") (pintype "input"))
    )
    (net (code "35") (name "VDD_5V{slash}3.3V") (class "Default")
      (node (ref "C7") (pin "1") (pinfunction "1_1") (pintype "input"))
      (node (ref "C8") (pin "1") (pinfunction "1_1") (pintype "input"))
      (node (ref "C9") (pin "1") (pinfunction "1_1") (pintype "input"))
      (node (ref "H1") (pin "1") (pinfunction "1_1") (pintype "input"))
      (node (ref "LED1") (pin "1") (pinfunction "A_1") (pintype "input"))
      (node (ref "LED2") (pin "1") (pinfunction "+_1") (pintype "input"))
      (node (ref "LED3") (pin "1") (pinfunction "A_1") (pintype "input"))
      (node (ref "R13") (pin "2") (pinfunction "2_2") (pintype "input"))
      (node (ref "R14") (pin "2") (pinfunction "2_2") (pintype "input"))
      (node (ref "R15") (pin "2") (pinfunction "2_2") (pintype "input"))
      (node (ref "R16") (pin "2") (pinfunction "2_2") (pintype "input"))
      (node (ref "R17") (pin "2") (pinfunction "2_2") (pintype "input"))
      (node (ref "R21") (pin "2") (pinfunction "2_2") (pintype "input"))
      (node (ref "R3") (pin "2") (pinfunction "2_2") (pintype "input"))
      (node (ref "R4") (pin "1") (pinfunction "1_1") (pintype "input"))
      (node (ref "R7") (pin "2") (pinfunction "2_2") (pintype "input"))
      (node (ref "R8") (pin "2") (pinfunction "2_2") (pintype "input"))
      (node (ref "SW1") (pin "1") (pinfunction "1_1") (pintype "input"))
      (node (ref "SW1") (pin "2") (pinfunction "2_2") (pintype "input"))
      (node (ref "U1") (pin "9") (pinfunction "VDD_9") (pintype "input"))
      (node (ref "U5") (pin "2") (pinfunction "2_2") (pintype "input"))
    )
    (net (code "36") (name "unconnected-(U3-VOUT-Pad2)") (class "Default")
      (node (ref "U3") (pin "2") (pinfunction "VOUT_2") (pintype "input+no_connect"))
    )
  )
)
